# DI8bitbox.net
KiCad netlist of a schematic drawn in EAGLE
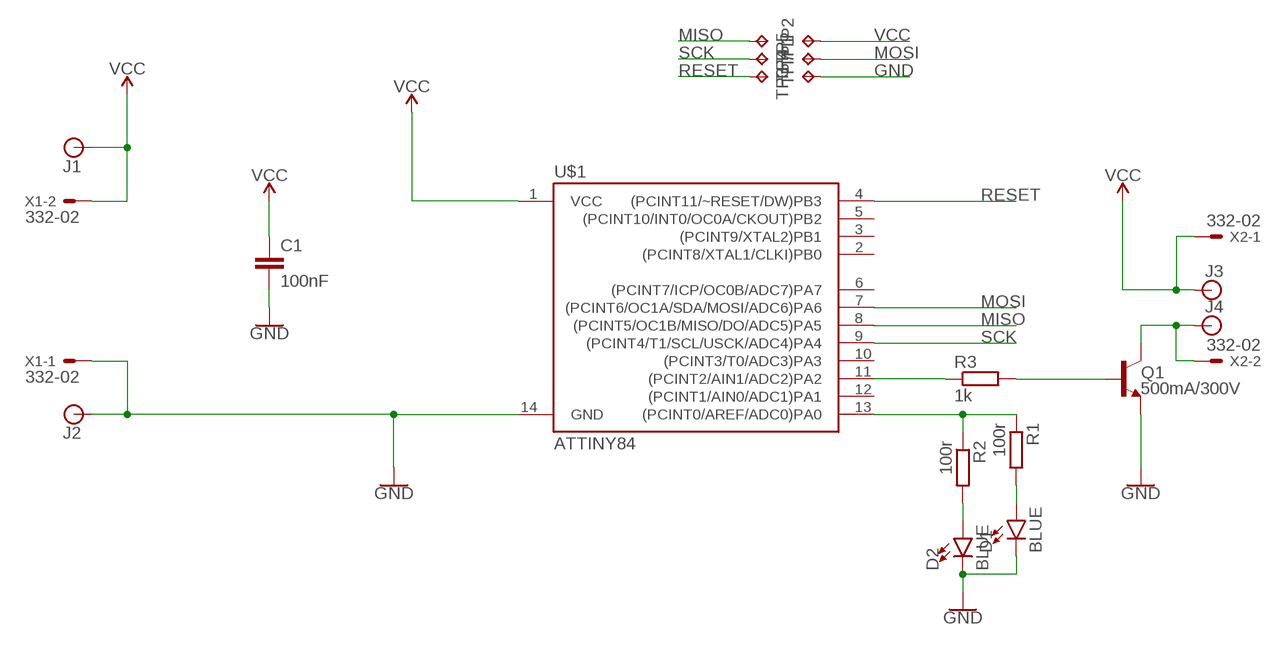
[diagram p0: schematic, sheet 1]

(export (version "E")
  (design (tool "Eeschema 10.0.6"))
  (components
    (comp (ref "C1")
      (value "100nF")
      (footprint "eagle-import:1206")
      (libsource (lib "eagle-import") (part "10UF-1206-6.3V-20%"))
    )
    (comp (ref "D1")
      (value "BLUE")
      (footprint "eagle-import:LED-1206")
      (libsource (lib "eagle-import") (part "LED-BLUE1206"))
    )
    (comp (ref "D2")
      (value "BLUE")
      (footprint "eagle-import:LED-1206")
      (libsource (lib "eagle-import") (part "LED-BLUE1206"))
    )
    (comp (ref "J1")
      (value "BANANA_CONN")
      (footprint "eagle-import:BANANA_CONN")
      (libsource (lib "eagle-import") (part "BANANA_CONN"))
    )
    (comp (ref "J2")
      (value "BANANA_CONN")
      (footprint "eagle-import:BANANA_CONN")
      (libsource (lib "eagle-import") (part "BANANA_CONN"))
    )
    (comp (ref "J3")
      (value "BANANA_CONN")
      (footprint "eagle-import:BANANA_CONN")
      (libsource (lib "eagle-import") (part "BANANA_CONN"))
    )
    (comp (ref "J4")
      (value "BANANA_CONN")
      (footprint "eagle-import:BANANA_CONN")
      (libsource (lib "eagle-import") (part "BANANA_CONN"))
    )
    (comp (ref "Q1")
      (value "500mA/300V")
      (footprint "eagle-import:SOT23-3")
      (libsource (lib "eagle-import") (part "TRANS_NPN-MMBTA42"))
    )
    (comp (ref "R1")
      (value "100r")
      (footprint "eagle-import:M0805")
      (libsource (lib "eagle-import") (part "R-EU_M0805"))
    )
    (comp (ref "R2")
      (value "100r")
      (footprint "eagle-import:M0805")
      (libsource (lib "eagle-import") (part "R-EU_M0805"))
    )
    (comp (ref "R3")
      (value "1k")
      (footprint "eagle-import:M0805")
      (libsource (lib "eagle-import") (part "R-EU_M0805"))
    )
    (comp (ref "TP1")
      (value "TPTP18R")
      (footprint "eagle-import:TP18R")
      (libsource (lib "eagle-import") (part "TPTP18R"))
    )
    (comp (ref "TP2")
      (value "TPTP18R")
      (footprint "eagle-import:TP18R")
      (libsource (lib "eagle-import") (part "TPTP18R"))
    )
    (comp (ref "TP3")
      (value "TPTP18R")
      (footprint "eagle-import:TP18R")
      (libsource (lib "eagle-import") (part "TPTP18R"))
    )
    (comp (ref "TP4")
      (value "TPTP18R")
      (footprint "eagle-import:TP18R")
      (libsource (lib "eagle-import") (part "TPTP18R"))
    )
    (comp (ref "TP5")
      (value "TPTP18R")
      (footprint "eagle-import:TP18R")
      (libsource (lib "eagle-import") (part "TPTP18R"))
    )
    (comp (ref "TP7")
      (value "TPTP18R")
      (footprint "eagle-import:TP18R")
      (libsource (lib "eagle-import") (part "TPTP18R"))
    )
    (comp (ref "U$1")
      (value "ATTINY84")
      (footprint "eagle-import:SO14")
      (libsource (lib "eagle-import") (part "ATTINY84"))
    )
    (comp (ref "X1")
      (value "332-02")
      (footprint "eagle-import:332-02")
      (libsource (lib "eagle-import") (part "332-02"))
    )
    (comp (ref "X2")
      (value "332-02")
      (footprint "eagle-import:332-02")
      (libsource (lib "eagle-import") (part "332-02"))
    )
  )
  (nets
    (net (code "1") (name "/MISO") (class "Default")
      (node (ref "TP5") (pin "TP") (pinfunction "TP_TP") (pintype "input"))
      (node (ref "U$1") (pin "8") (pinfunction "(PCINT5/OC1B/MISO/DO/ADC5)PA5_8") (pintype "bidirectional"))
    )
    (net (code "2") (name "/MOSI") (class "Default")
      (node (ref "TP1") (pin "TP") (pinfunction "TP_TP") (pintype "input"))
      (node (ref "U$1") (pin "7") (pinfunction "(PCINT6/OC1A/SDA/MOSI/ADC6)PA6_7") (pintype "bidirectional"))
    )
    (net (code "3") (name "/RESET") (class "Default")
      (node (ref "TP3") (pin "TP") (pinfunction "TP_TP") (pintype "input"))
      (node (ref "U$1") (pin "4") (pinfunction "(PCINT11/~{RESET/DW})PB3_4") (pintype "bidirectional"))
    )
    (net (code "4") (name "/SCK") (class "Default")
      (node (ref "TP4") (pin "TP") (pinfunction "TP_TP") (pintype "input"))
      (node (ref "U$1") (pin "9") (pinfunction "(PCINT4/T1/SCL/USCK/ADC4)PA4_9") (pintype "bidirectional"))
    )
    (net (code "5") (name "GND") (class "Default")
      (node (ref "C1") (pin "2") (pinfunction "2_2") (pintype "passive"))
      (node (ref "D1") (pin "C") (pinfunction "C_C") (pintype "passive"))
      (node (ref "D2") (pin "C") (pinfunction "C_C") (pintype "passive"))
      (node (ref "J2") (pin "P$1") (pinfunction "1_P$1") (pintype "passive"))
      (node (ref "Q1") (pin "2") (pinfunction "E_2") (pintype "passive"))
      (node (ref "TP7") (pin "TP") (pinfunction "TP_TP") (pintype "input"))
      (node (ref "U$1") (pin "14") (pinfunction "GND_14") (pintype "bidirectional"))
      (node (ref "X1") (pin "1") (pinfunction "S_1") (pintype "passive"))
    )
    (net (code "6") (name "Net-(D1-PadA)") (class "Default")
      (node (ref "D1") (pin "A") (pinfunction "A_A") (pintype "passive"))
      (node (ref "R1") (pin "2") (pinfunction "2_2") (pintype "passive"))
    )
    (net (code "7") (name "Net-(D2-PadA)") (class "Default")
      (node (ref "D2") (pin "A") (pinfunction "A_A") (pintype "passive"))
      (node (ref "R2") (pin "2") (pinfunction "2_2") (pintype "passive"))
    )
    (net (code "8") (name "Net-(J4-1)") (class "Default")
      (node (ref "J4") (pin "P$1") (pinfunction "1_P$1") (pintype "passive"))
      (node (ref "Q1") (pin "3") (pinfunction "C_3") (pintype "passive"))
      (node (ref "X2") (pin "2") (pinfunction "S_2") (pintype "passive"))
    )
    (net (code "9") (name "Net-(Q1-B)") (class "Default")
      (node (ref "Q1") (pin "1") (pinfunction "B_1") (pintype "passive"))
      (node (ref "R3") (pin "2") (pinfunction "2_2") (pintype "passive"))
    )
    (net (code "10") (name "Net-(U$1-(PCINT0{slash}AREF{slash}ADC0)PA0)") (class "Default")
      (node (ref "R1") (pin "1") (pinfunction "1_1") (pintype "passive"))
      (node (ref "R2") (pin "1") (pinfunction "1_1") (pintype "passive"))
      (node (ref "U$1") (pin "13") (pinfunction "(PCINT0/AREF/ADC0)PA0_13") (pintype "bidirectional"))
    )
    (net (code "11") (name "Net-(U$1-(PCINT2{slash}AIN1{slash}ADC2)PA2)") (class "Default")
      (node (ref "R3") (pin "1") (pinfunction "1_1") (pintype "passive"))
      (node (ref "U$1") (pin "11") (pinfunction "(PCINT2/AIN1/ADC2)PA2_11") (pintype "bidirectional"))
    )
    (net (code "12") (name "VCC") (class "Default")
      (node (ref "C1") (pin "1") (pinfunction "1_1") (pintype "passive"))
      (node (ref "J1") (pin "P$1") (pinfunction "1_P$1") (pintype "passive"))
      (node (ref "J3") (pin "P$1") (pinfunction "1_P$1") (pintype "passive"))
      (node (ref "TP2") (pin "TP") (pinfunction "TP_TP") (pintype "input"))
      (node (ref "U$1") (pin "1") (pinfunction "VCC_1") (pintype "bidirectional"))
      (node (ref "X1") (pin "2") (pinfunction "S_2") (pintype "passive"))
      (node (ref "X2") (pin "1") (pinfunction "S_1") (pintype "passive"))
    )
    (net (code "13") (name "unconnected-(U$1-(PCINT1{slash}AIN0{slash}ADC1)PA1-Pad12)") (class "Default")
      (node (ref "U$1") (pin "12") (pinfunction "(PCINT1/AIN0/ADC1)PA1_12") (pintype "bidirectional"))
    )
    (net (code "14") (name "unconnected-(U$1-(PCINT3{slash}T0{slash}ADC3)PA3-Pad10)") (class "Default")
      (node (ref "U$1") (pin "10") (pinfunction "(PCINT3/T0/ADC3)PA3_10") (pintype "bidirectional"))
    )
    (net (code "15") (name "unconnected-(U$1-(PCINT7{slash}ICP{slash}OC0B{slash}ADC7)PA7-Pad6)") (class "Default")
      (node (ref "U$1") (pin "6") (pinfunction "(PCINT7/ICP/OC0B/ADC7)PA7_6") (pintype "bidirectional"))
    )
    (net (code "16") (name "unconnected-(U$1-(PCINT8{slash}XTAL1{slash}CLKI)PB0-Pad2)") (class "Default")
      (node (ref "U$1") (pin "2") (pinfunction "(PCINT8/XTAL1/CLKI)PB0_2") (pintype "bidirectional"))
    )
    (net (code "17") (name "unconnected-(U$1-(PCINT9{slash}XTAL2)PB1-Pad3)") (class "Default")
      (node (ref "U$1") (pin "3") (pinfunction "(PCINT9/XTAL2)PB1_3") (pintype "bidirectional"))
    )
    (net (code "18") (name "unconnected-(U$1-(PCINT10{slash}INT0{slash}OC0A{slash}CKOUT)PB2-Pad5)") (class "Default")
      (node (ref "U$1") (pin "5") (pinfunction "(PCINT10/INT0/OC0A/CKOUT)PB2_5") (pintype "bidirectional"))
    )
  )
)
